# Sensor_Box_PWR_AC.net
KiCad netlist of a schematic drawn in Altium Designer
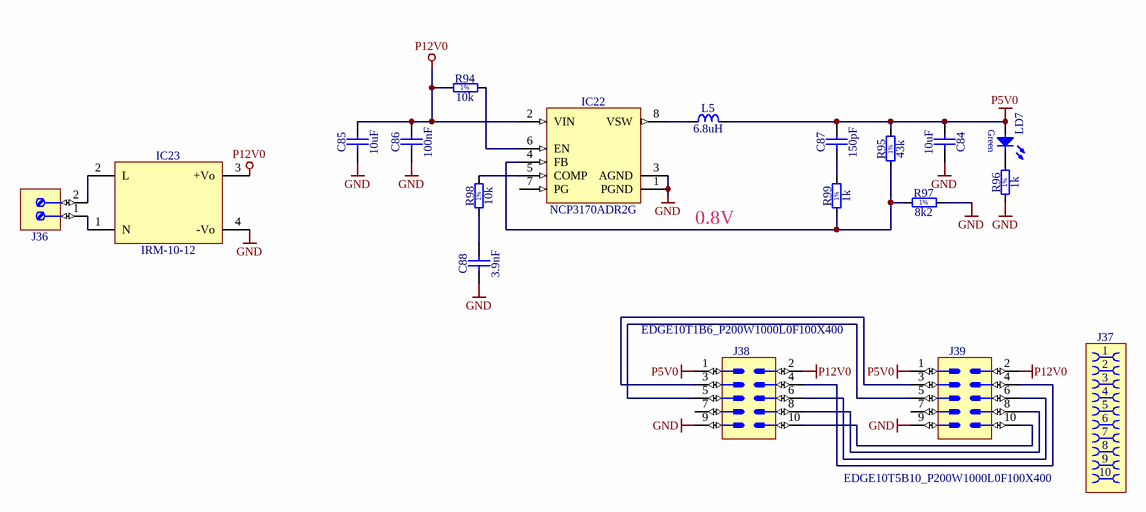
[diagram p0: Sensor_Box_PWR_AC.SchDoc]

(export (version "E")
  (design (tool "Eeschema 10.0.6"))
  (components
    (comp (ref "C84")
      (value "10uF")
      (footprint "CAPC2012X135N")
      (description "Non-polarised capacitor")
      (fields
        (field (name "PART NUMBER") "CC0805_10UF_16V_10%_X5R")
        (field (name "VOLTAGE") "16V")
        (field (name "AUTHOR") "CERN DEM JLC")
      )
      (libsource (lib "Capacitors") (part "Capacitor - non polarized"))
    )
    (comp (ref "C85")
      (value "10uF")
      (footprint "CAPC2012X135N")
      (description "Non-polarised capacitor")
      (fields
        (field (name "PART NUMBER") "CC0805_10UF_16V_10%_X5R")
        (field (name "VOLTAGE") "16V")
        (field (name "AUTHOR") "CERN DEM JLC")
      )
      (libsource (lib "Capacitors") (part "Capacitor - non polarized"))
    )
    (comp (ref "C86")
      (value "100nF")
      (footprint "CAPC1005X55N")
      (description "Non-polarised capacitor")
      (fields
        (field (name "PART NUMBER") "CC0402_100NF_16V_10%_X5R")
        (field (name "VOLTAGE") "16V")
        (field (name "AUTHOR") "CERN DEM JLC")
      )
      (libsource (lib "Capacitors") (part "Capacitor - non polarized"))
    )
    (comp (ref "C87")
      (value "150pF")
      (footprint "CAPC1608X87N")
      (description "Non-polarised capacitor")
      (fields
        (field (name "PART NUMBER") "CC0603_150PF_50V_1%_NP0")
        (field (name "VOLTAGE") "50V")
        (field (name "AUTHOR") "CERN DEM MR")
      )
      (libsource (lib "Capacitors") (part "Capacitor - non polarized"))
    )
    (comp (ref "C88")
      (value "3.9nF")
      (footprint "CAPC1608X87N")
      (description "Non-polarised capacitor")
      (fields
        (field (name "PART NUMBER") "CC0603_3.9NF_50V_5%_X7R")
        (field (name "VOLTAGE") "50V")
        (field (name "AUTHOR") "CERN DEM JLC")
      )
      (libsource (lib "Capacitors") (part "Capacitor - non polarized"))
    )
    (comp (ref "IC22")
      (value "NCP3170ADR2G")
      (footprint "SOIC127P600X175-8N")
      (description "Synchronous PWM Switching Converter")
      (fields (field (name "MANUFACTURER") "ON SEMICONDUCTOR") (field (name "AUTHOR") "CERN DEM MR"))
      (libsource (lib "ICs And Semiconductors") (part "NCP3170ADR2G"))
    )
    (comp (ref "IC23")
      (value "IRM-10-12")
      (footprint "PWS_MEANWELL_IRM-10")
      (description "Power Supply")
      (fields (field (name "MANUFACTURER") "MEAN WELL") (field (name "AUTHOR") "CERN DEM MR"))
      (libsource (lib "ICs And Semiconductors") (part "PWS 1N 2L 3Vo+ 4Vo-"))
    )
    (comp (ref "J36")
      (value "~")
      (footprint "PHOENIX_1751248")
      (description "Terminal Block, 2 Positions, Screw Connection")
      (fields
        (field (name "PART NUMBER") "PHOENIX_1751248")
        (field (name "MANUFACTURER") "PHOENIX CONTACT")
        (field (name "AUTHOR") "CERN DEM JLC")
      )
      (libsource (lib "Connectors") (part "Terminal Block_2 Positions_Screw Connection"))
    )
    (comp (ref "J37")
      (value "~")
      (footprint "AVX_00 9159 010 061 916")
      (description "Open Ended Card Edge Connector, 9159 Series")
      (fields
        (field (name "PART NUMBER") "AVX_00 9159 010 061 916")
        (field (name "MANUFACTURER") "AVX")
        (field (name "AUTHOR") "CERN DEM MR")
      )
      (libsource (lib "Connectors") (part "AVX_00 9159 010 061 916"))
    )
    (comp (ref "J38")
      (value "~")
      (footprint "EDGE10T1B6_P200W1000L0F100X400")
      (description "PCB Edge Connector 10 (2x5)")
      (fields
        (field (name "PART NUMBER") "EDGE10T1B6_P200W1000L0F100X400")
        (field (name "AUTHOR") "CERN DEM MR")
      )
      (libsource (lib "Connectors") (part "PCB Edge Connector 10 (2x5)"))
    )
    (comp (ref "J39")
      (value "~")
      (footprint "EDGE10T5B10_P200W1000L0F100X400")
      (description "PCB Edge Connector 10 (2x5)")
      (fields
        (field (name "PART NUMBER") "EDGE10T5B10_P200W1000L0F100X400")
        (field (name "AUTHOR") "CERN DEM MR")
      )
      (libsource (lib "Connectors") (part "PCB Edge Connector 10 (2x5)"))
    )
    (comp (ref "L5")
      (value "6.8uH")
      (footprint "IND_BOURNS_SRU8043")
      (description "Inductor")
      (fields
        (field (name "PART NUMBER") "IND_6.8UH_30%_BOURNS_SRU8043")
        (field (name "POWER") "3.8A")
        (field (name "AUTHOR") "CERN DEM JMW")
      )
      (libsource (lib "Inductors & Transformers") (part "Inductor"))
    )
    (comp (ref "LD7")
      (value "Green")
      (footprint "LED_KINGBRIGHT_KPTR3216")
      (description "LED Green 1A 2C")
      (fields
        (field (name "PART NUMBER") "LED_KINGBRIGHT_KPTR-3216CGCK")
        (field (name "MANUFACTURER") "KINGBRIGHT")
        (field (name "AUTHOR") "CERN DEM MR")
      )
      (libsource (lib "ICs And Semiconductors") (part "LED_KINGBRIGHT_KPTR-3216CGCK"))
    )
    (comp (ref "R94")
      (value "10k")
      (footprint "RESC1005X40N")
      (description "Resistor - 1%")
      (fields
        (field (name "PART NUMBER") "R0402_10K_1%_0.0625W_100PPM")
        (field (name "POWER") "0.0625W")
        (field (name "AUTHOR") "CERN DEM JLC")
      )
      (libsource (lib "Resistors") (part "Resistor - 1%"))
    )
    (comp (ref "R95")
      (value "43k")
      (footprint "RESC1608X55N")
      (description "Resistor - 1%")
      (fields
        (field (name "PART NUMBER") "R0603_43K_1%_0.1W_100PPM")
        (field (name "POWER") "0.1W")
        (field (name "AUTHOR") "CERN DEM JLC")
      )
      (libsource (lib "Resistors") (part "Resistor - 1%"))
    )
    (comp (ref "R96")
      (value "1k")
      (footprint "RESC1005X40N")
      (description "Resistor - 1%")
      (fields
        (field (name "PART NUMBER") "R0402_1K_1%_0.0625W_100PPM")
        (field (name "POWER") "0.0625W")
        (field (name "AUTHOR") "CERN DEM JLC")
      )
      (libsource (lib "Resistors") (part "Resistor - 1%"))
    )
    (comp (ref "R97")
      (value "8k2")
      (footprint "RESC1608X55N")
      (description "Resistor - 1%")
      (fields
        (field (name "PART NUMBER") "R0603_8K2_1%_0.1W_100PPM")
        (field (name "POWER") "0.1W")
        (field (name "AUTHOR") "CERN DEM JLC")
      )
      (libsource (lib "Resistors") (part "Resistor - 1%"))
    )
    (comp (ref "R98")
      (value "10k")
      (footprint "RESC1005X40N")
      (description "Resistor - 1%")
      (fields
        (field (name "PART NUMBER") "R0402_10K_1%_0.0625W_100PPM")
        (field (name "POWER") "0.0625W")
        (field (name "AUTHOR") "CERN DEM JLC")
      )
      (libsource (lib "Resistors") (part "Resistor - 1%"))
    )
    (comp (ref "R99")
      (value "1k")
      (footprint "RESC1005X40N")
      (description "Resistor - 1%")
      (fields
        (field (name "PART NUMBER") "R0402_1K_1%_0.0625W_100PPM")
        (field (name "POWER") "0.0625W")
        (field (name "AUTHOR") "CERN DEM JLC")
      )
      (libsource (lib "Resistors") (part "Resistor - 1%"))
    )
  )
  (nets
    (net (code "1") (name "GND") (class "Default")
      (node (ref "C84") (pin "2") (pinfunction "2_2") (pintype "passive"))
      (node (ref "C85") (pin "1") (pinfunction "1_1") (pintype "passive"))
      (node (ref "C86") (pin "1") (pinfunction "1_1") (pintype "passive"))
      (node (ref "C88") (pin "1") (pinfunction "1_1") (pintype "passive"))
      (node (ref "IC22") (pin "1") (pinfunction "PGND_1") (pintype "power_in"))
      (node (ref "IC22") (pin "3") (pinfunction "AGND_3") (pintype "power_in"))
      (node (ref "IC23") (pin "4") (pinfunction "-Vo_4") (pintype "power_in"))
      (node (ref "J38") (pin "9") (pinfunction "9_9") (pintype "bidirectional"))
      (node (ref "J39") (pin "9") (pinfunction "9_9") (pintype "bidirectional"))
      (node (ref "R96") (pin "1") (pinfunction "1_1") (pintype "passive"))
      (node (ref "R97") (pin "2") (pinfunction "2_2") (pintype "passive"))
    )
    (net (code "2") (name "Net-(C87-Pad1)") (class "Default")
      (node (ref "C87") (pin "1") (pinfunction "1_1") (pintype "passive"))
      (node (ref "R99") (pin "2") (pinfunction "2_2") (pintype "passive"))
    )
    (net (code "3") (name "Net-(C88-Pad2)") (class "Default")
      (node (ref "C88") (pin "2") (pinfunction "2_2") (pintype "passive"))
      (node (ref "R98") (pin "1") (pinfunction "1_1") (pintype "passive"))
    )
    (net (code "4") (name "Net-(IC22-COMP)") (class "Default")
      (node (ref "IC22") (pin "5") (pinfunction "COMP_5") (pintype "input"))
      (node (ref "R98") (pin "2") (pinfunction "2_2") (pintype "passive"))
    )
    (net (code "5") (name "Net-(IC22-EN)") (class "Default")
      (node (ref "IC22") (pin "6") (pinfunction "EN_6") (pintype "input"))
      (node (ref "R94") (pin "2") (pinfunction "2_2") (pintype "passive"))
    )
    (net (code "6") (name "Net-(IC22-FB)") (class "Default")
      (node (ref "IC22") (pin "4") (pinfunction "FB_4") (pintype "input"))
      (node (ref "R95") (pin "1") (pinfunction "1_1") (pintype "passive"))
      (node (ref "R97") (pin "1") (pinfunction "1_1") (pintype "passive"))
      (node (ref "R99") (pin "1") (pinfunction "1_1") (pintype "passive"))
    )
    (net (code "7") (name "Net-(IC22-VSW)") (class "Default")
      (node (ref "IC22") (pin "8") (pinfunction "VSW_8") (pintype "output"))
      (node (ref "L5") (pin "1") (pinfunction "1_1") (pintype "passive"))
    )
    (net (code "8") (name "Net-(IC23-L)") (class "Default")
      (node (ref "IC23") (pin "2") (pinfunction "L_2") (pintype "power_in"))
      (node (ref "J36") (pin "2") (pinfunction "2_2") (pintype "bidirectional"))
    )
    (net (code "9") (name "Net-(IC23-N)") (class "Default")
      (node (ref "IC23") (pin "1") (pinfunction "N_1") (pintype "power_in"))
      (node (ref "J36") (pin "1") (pinfunction "1_1") (pintype "bidirectional"))
    )
    (net (code "10") (name "Net-(J38-Pad3)") (class "Default")
      (node (ref "J38") (pin "3") (pinfunction "3_3") (pintype "bidirectional"))
      (node (ref "J39") (pin "3") (pinfunction "3_3") (pintype "bidirectional"))
    )
    (net (code "11") (name "Net-(J38-Pad4)") (class "Default")
      (node (ref "J38") (pin "4") (pinfunction "4_4") (pintype "bidirectional"))
      (node (ref "J39") (pin "4") (pinfunction "4_4") (pintype "bidirectional"))
    )
    (net (code "12") (name "Net-(J38-Pad5)") (class "Default")
      (node (ref "J38") (pin "5") (pinfunction "5_5") (pintype "bidirectional"))
      (node (ref "J39") (pin "5") (pinfunction "5_5") (pintype "bidirectional"))
    )
    (net (code "13") (name "Net-(J38-Pad6)") (class "Default")
      (node (ref "J38") (pin "6") (pinfunction "6_6") (pintype "bidirectional"))
      (node (ref "J39") (pin "6") (pinfunction "6_6") (pintype "bidirectional"))
    )
    (net (code "14") (name "Net-(J38-Pad8)") (class "Default")
      (node (ref "J38") (pin "8") (pinfunction "8_8") (pintype "bidirectional"))
      (node (ref "J39") (pin "8") (pinfunction "8_8") (pintype "bidirectional"))
    )
    (net (code "15") (name "Net-(J38-Pad10)") (class "Default")
      (node (ref "J38") (pin "10") (pinfunction "10_10") (pintype "bidirectional"))
      (node (ref "J39") (pin "10") (pinfunction "10_10") (pintype "bidirectional"))
    )
    (net (code "16") (name "Net-(LD7-C)") (class "Default")
      (node (ref "LD7") (pin "1") (pinfunction "C_1") (pintype "passive"))
      (node (ref "R96") (pin "2") (pinfunction "2_2") (pintype "passive"))
    )
    (net (code "17") (name "P5V0") (class "Default")
      (node (ref "C84") (pin "1") (pinfunction "1_1") (pintype "passive"))
      (node (ref "C87") (pin "2") (pinfunction "2_2") (pintype "passive"))
      (node (ref "J38") (pin "1") (pinfunction "1_1") (pintype "bidirectional"))
      (node (ref "J39") (pin "1") (pinfunction "1_1") (pintype "bidirectional"))
      (node (ref "L5") (pin "2") (pinfunction "2_2") (pintype "passive"))
      (node (ref "LD7") (pin "2") (pinfunction "A_2") (pintype "passive"))
      (node (ref "R95") (pin "2") (pinfunction "2_2") (pintype "passive"))
    )
    (net (code "18") (name "P12V0") (class "Default")
      (node (ref "C85") (pin "2") (pinfunction "2_2") (pintype "passive"))
      (node (ref "C86") (pin "2") (pinfunction "2_2") (pintype "passive"))
      (node (ref "IC22") (pin "2") (pinfunction "VIN_2") (pintype "input"))
      (node (ref "IC23") (pin "3") (pinfunction "+Vo_3") (pintype "power_in"))
      (node (ref "J38") (pin "2") (pinfunction "2_2") (pintype "bidirectional"))
      (node (ref "J39") (pin "2") (pinfunction "2_2") (pintype "bidirectional"))
      (node (ref "R94") (pin "1") (pinfunction "1_1") (pintype "passive"))
    )
    (net (code "19") (name "unconnected-(IC22-PG-Pad7)") (class "Default")
      (node (ref "IC22") (pin "7") (pinfunction "PG_7") (pintype "input"))
    )
    (net (code "20") (name "unconnected-(J38-Pad7)") (class "Default")
      (node (ref "J38") (pin "7") (pinfunction "7_7") (pintype "bidirectional"))
    )
    (net (code "21") (name "unconnected-(J39-Pad7)") (class "Default")
      (node (ref "J39") (pin "7") (pinfunction "7_7") (pintype "bidirectional"))
    )
  )
)
